# GSM.net
KiCad netlist of a schematic drawn in Altium Designer
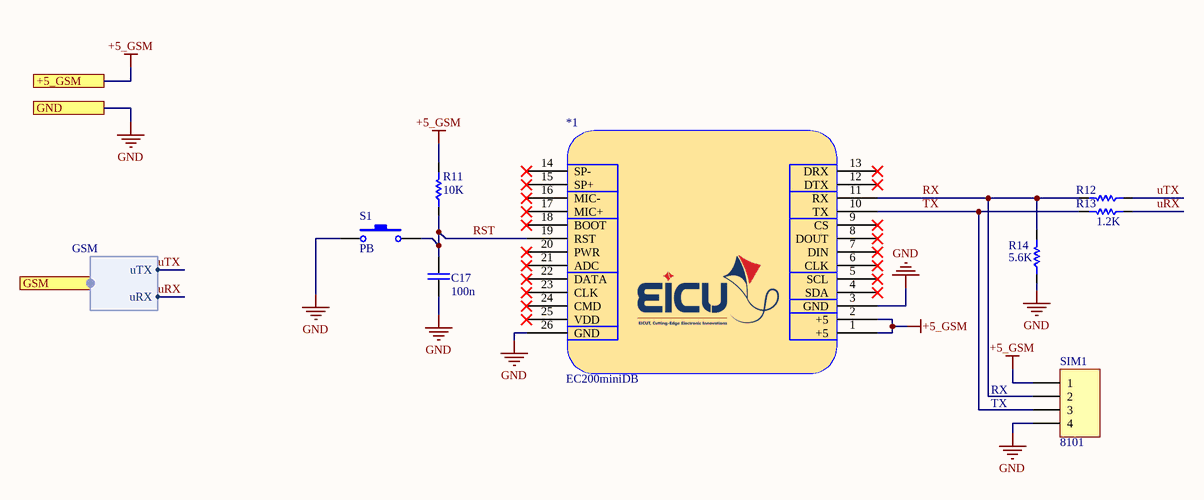
[diagram p0: GSM.SchDoc]

(export (version "E")
  (design (tool "Eeschema 10.0.6"))
  (components
    (comp (ref "*1")
      (value "EC200miniDB")
      (footprint "PCBComponent_1")
      (description "EICUT.com")
      (libsource (lib "EC200miniDB") (part "EC200miniDB"))
    )
    (comp (ref "C17")
      (value "100n")
      (footprint "CAP 1206/3216")
      (description "Bipolar ceramic capacitor SMD")
      (fields (field (name "VALIDATION") "Valid"))
      (libsource (lib "aKaReZa") (part "Cap_Multi_SMD_100nF_1206"))
    )
    (comp (ref "R11")
      (value "10K")
      (footprint "RES 1206 (3216X08L)")
      (description "Resistor")
      (fields (field (name "VALIDATION") "Valid"))
      (libsource (lib "aKaReZa") (part "Res_SMD_1206"))
    )
    (comp (ref "R12")
      (value "47K")
      (footprint "RES 1206 (3216X08L)")
      (description "Resistor")
      (fields (field (name "VALIDATION") "Valid"))
      (libsource (lib "aKaReZa") (part "Res_SMD_1206"))
    )
    (comp (ref "R13")
      (value "1.2K")
      (footprint "RES 1206 (3216X08L)")
      (description "Resistor")
      (fields (field (name "Comment") "1K") (field (name "VALIDATION") "Valid"))
      (libsource (lib "aKaReZa") (part "Res_SMD_1206"))
    )
    (comp (ref "R14")
      (value "5.6K")
      (footprint "RES 1206 (3216X08L)")
      (description "Resistor")
      (fields (field (name "VALIDATION") "Valid"))
      (libsource (lib "aKaReZa") (part "Res_SMD_1206"))
    )
    (comp (ref "S1")
      (value "PB")
      (footprint "SW_PB_SMD_2PIN_SPST_6X3X2")
      (description "SMT Tactile ‎Switch")
      (fields (field (name "VALIDATION") "Valid"))
      (libsource (lib "aKaReZa") (part "SW_PushButton_2_SMD"))
    )
    (comp (ref "SIM1")
      (value "4")
      (footprint "HDR_THT_4F_2.54mm")
      (description "Header, single row, 4 pin")
      (fields (field (name "INFLOW") "8101") (field (name "VALIDATION") "NT"))
      (libsource (lib "aKaReZa") (part "Con_FPH_4x1_V_THT_2.54"))
    )
  )
  (nets
    (net (code "2") (name "+5_GSM") (class "Default")
      (node (ref "*1") (pin "1") (pinfunction "+5_1") (pintype "passive"))
      (node (ref "*1") (pin "2") (pinfunction "+5_2") (pintype "passive"))
      (node (ref "R11") (pin "2") (pinfunction "2_2") (pintype "passive"))
      (node (ref "SIM1") (pin "1") (pinfunction "1_1") (pintype "passive"))
    )
    (net (code "3") (name "/RST") (class "Default")
      (node (ref "*1") (pin "19") (pinfunction "RST_19") (pintype "passive"))
      (node (ref "C17") (pin "1") (pinfunction "1_1") (pintype "passive"))
      (node (ref "R11") (pin "1") (pinfunction "1_1") (pintype "passive"))
      (node (ref "S1") (pin "1") (pinfunction "1_1") (pintype "passive"))
    )
    (net (code "4") (name "/RX") (class "Default")
      (node (ref "*1") (pin "11") (pinfunction "RX_11") (pintype "passive"))
      (node (ref "R12") (pin "2") (pinfunction "2_2") (pintype "passive"))
      (node (ref "R14") (pin "2") (pinfunction "2_2") (pintype "passive"))
      (node (ref "SIM1") (pin "2") (pinfunction "2_2") (pintype "passive"))
    )
    (net (code "5") (name "/TX") (class "Default")
      (node (ref "*1") (pin "10") (pinfunction "TX_10") (pintype "passive"))
      (node (ref "R13") (pin "2") (pinfunction "2_2") (pintype "passive"))
      (node (ref "SIM1") (pin "3") (pinfunction "3_3") (pintype "passive"))
    )
    (net (code "6") (name "/uRX") (class "Default")
      (node (ref "R13") (pin "1") (pinfunction "1_1") (pintype "passive"))
    )
    (net (code "7") (name "/uTX") (class "Default")
      (node (ref "R12") (pin "1") (pinfunction "1_1") (pintype "passive"))
    )
    (net (code "9") (name "GND") (class "Default")
      (node (ref "*1") (pin "26") (pinfunction "GND_26") (pintype "passive"))
      (node (ref "*1") (pin "3") (pinfunction "GND_3") (pintype "passive"))
      (node (ref "C17") (pin "2") (pinfunction "2_2") (pintype "passive"))
      (node (ref "R14") (pin "1") (pinfunction "1_1") (pintype "passive"))
      (node (ref "S1") (pin "2") (pinfunction "2_2") (pintype "passive"))
      (node (ref "SIM1") (pin "4") (pinfunction "4_4") (pintype "passive"))
    )
    (net (code "10") (name "unconnected-(*1-ADC-Pad21)") (class "Default")
      (node (ref "*1") (pin "21") (pinfunction "ADC_21") (pintype "passive+no_connect"))
    )
    (net (code "11") (name "unconnected-(*1-BOOT-Pad18)") (class "Default")
      (node (ref "*1") (pin "18") (pinfunction "BOOT_18") (pintype "passive+no_connect"))
    )
    (net (code "12") (name "unconnected-(*1-CLK-Pad6)") (class "Default")
      (node (ref "*1") (pin "6") (pinfunction "CLK_6") (pintype "passive+no_connect"))
    )
    (net (code "13") (name "unconnected-(*1-CLK-Pad23)") (class "Default")
      (node (ref "*1") (pin "23") (pinfunction "CLK_23") (pintype "passive+no_connect"))
    )
    (net (code "14") (name "unconnected-(*1-CMD-Pad24)") (class "Default")
      (node (ref "*1") (pin "24") (pinfunction "CMD_24") (pintype "passive+no_connect"))
    )
    (net (code "15") (name "unconnected-(*1-CS-Pad9)") (class "Default")
      (node (ref "*1") (pin "9") (pinfunction "CS_9") (pintype "passive+no_connect"))
    )
    (net (code "16") (name "unconnected-(*1-DATA-Pad22)") (class "Default")
      (node (ref "*1") (pin "22") (pinfunction "DATA_22") (pintype "passive+no_connect"))
    )
    (net (code "17") (name "unconnected-(*1-DIN-Pad7)") (class "Default")
      (node (ref "*1") (pin "7") (pinfunction "DIN_7") (pintype "passive+no_connect"))
    )
    (net (code "18") (name "unconnected-(*1-DOUT-Pad8)") (class "Default")
      (node (ref "*1") (pin "8") (pinfunction "DOUT_8") (pintype "passive+no_connect"))
    )
    (net (code "19") (name "unconnected-(*1-DRX-Pad13)") (class "Default")
      (node (ref "*1") (pin "13") (pinfunction "DRX_13") (pintype "passive+no_connect"))
    )
    (net (code "20") (name "unconnected-(*1-DTX-Pad12)") (class "Default")
      (node (ref "*1") (pin "12") (pinfunction "DTX_12") (pintype "passive+no_connect"))
    )
    (net (code "21") (name "unconnected-(*1-MIC+-Pad17)") (class "Default")
      (node (ref "*1") (pin "17") (pinfunction "MIC+_17") (pintype "passive+no_connect"))
    )
    (net (code "22") (name "unconnected-(*1-MIC--Pad16)") (class "Default")
      (node (ref "*1") (pin "16") (pinfunction "MIC-_16") (pintype "passive+no_connect"))
    )
    (net (code "23") (name "unconnected-(*1-PWR-Pad20)") (class "Default")
      (node (ref "*1") (pin "20") (pinfunction "PWR_20") (pintype "passive+no_connect"))
    )
    (net (code "24") (name "unconnected-(*1-SCL-Pad5)") (class "Default")
      (node (ref "*1") (pin "5") (pinfunction "SCL_5") (pintype "passive+no_connect"))
    )
    (net (code "25") (name "unconnected-(*1-SDA-Pad4)") (class "Default")
      (node (ref "*1") (pin "4") (pinfunction "SDA_4") (pintype "passive+no_connect"))
    )
    (net (code "26") (name "unconnected-(*1-SP+-Pad15)") (class "Default")
      (node (ref "*1") (pin "15") (pinfunction "SP+_15") (pintype "passive+no_connect"))
    )
    (net (code "27") (name "unconnected-(*1-SP--Pad14)") (class "Default")
      (node (ref "*1") (pin "14") (pinfunction "SP-_14") (pintype "passive+no_connect"))
    )
    (net (code "28") (name "unconnected-(*1-VDD-Pad25)") (class "Default")
      (node (ref "*1") (pin "25") (pinfunction "VDD_25") (pintype "passive+no_connect"))
    )
  )
)
